# Vehicule.net
KiCad netlist of a schematic drawn in Altium Designer
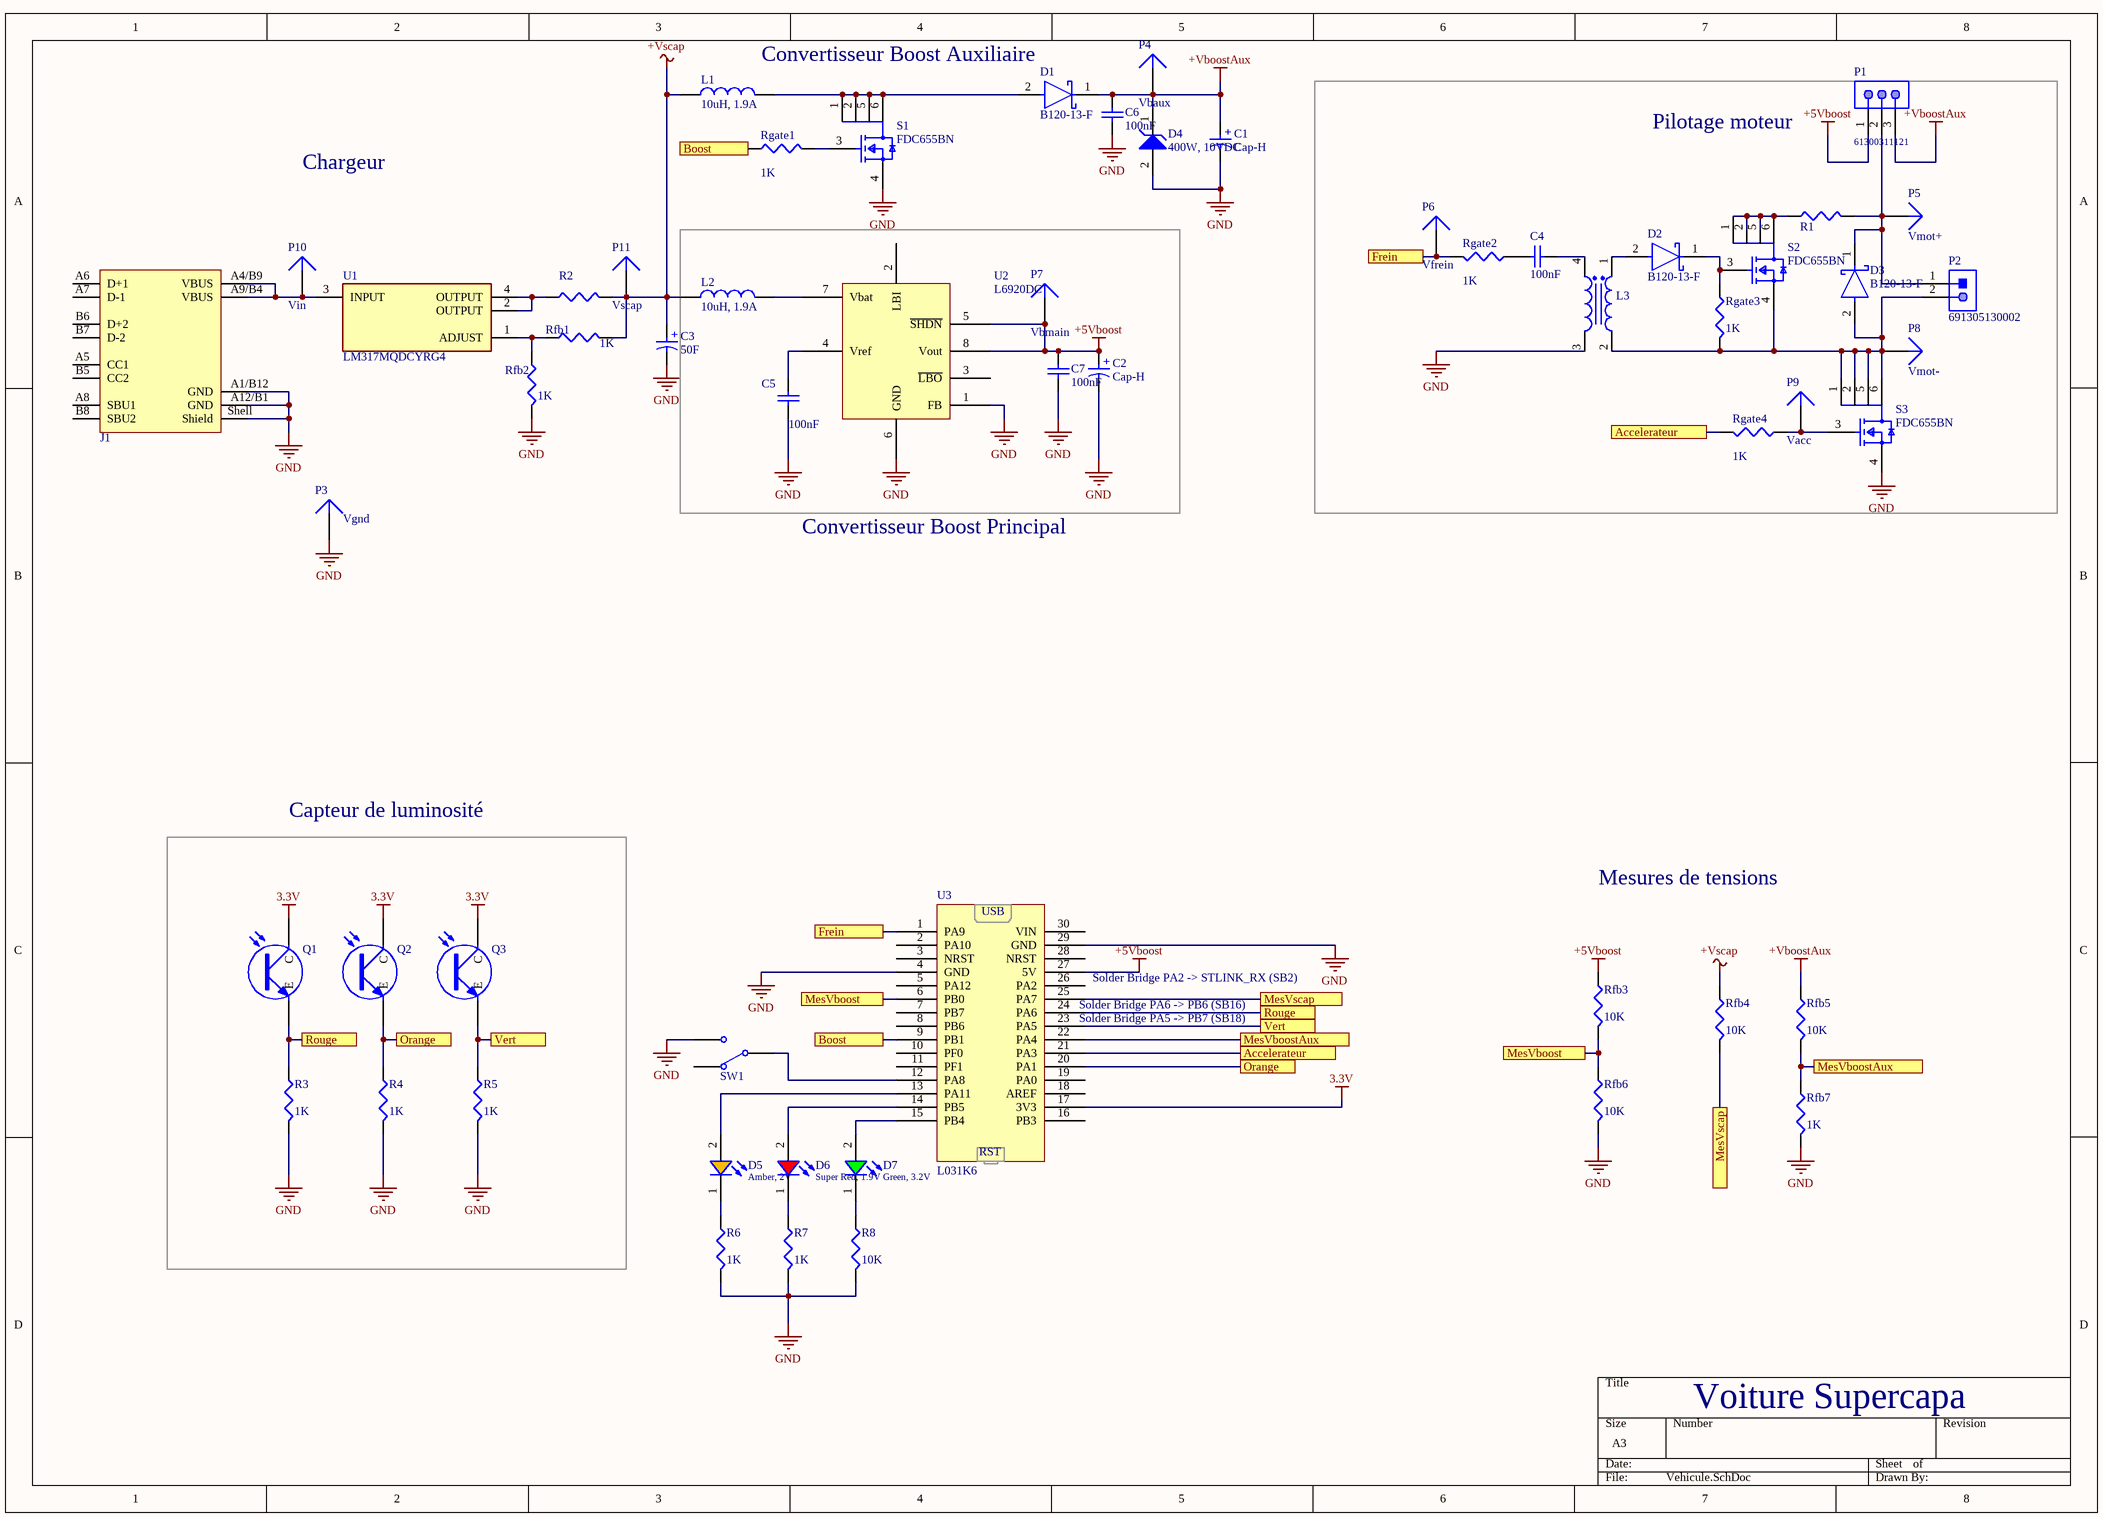
[diagram p0: Vehicule.SchDoc]

(export (version "E")
  (design (tool "Eeschema 10.0.6"))
  (components
    (comp (ref "C1")
      (value "Cap-H")
      (footprint "CAP-8x20")
      (description "Capacitor 8x20 H")
      (fields
        (field (name "MANUFACTURER PART NUMBER") "850617022002")
        (field (name "MANUFACTURER") "Wurth Elektronik")
      )
      (libsource (lib "Voiture-Supercap") (part "CAP-WE-8X20H"))
    )
    (comp (ref "C2")
      (value "Cap-H")
      (footprint "CAP-8x20")
      (description "Capacitor 8x20 H")
      (fields
        (field (name "MANUFACTURER PART NUMBER") "850617022002")
        (field (name "MANUFACTURER") "Wurth Elektronik")
      )
      (libsource (lib "Voiture-Supercap") (part "CAP-WE-8X20H"))
    )
    (comp (ref "C3")
      (value "50F")
      (footprint "SuperCap Couchee")
      (description "WCAP-STSC Supercapacitors (EDLCs), THT, D18 x H40mm, 50F, 2.7VDC")
      (fields
        (field (name "MANUFACTURER PART NUMBER") "850617022002")
        (field (name "MANUFACTURER") "Wurth Elektronik")
      )
      (libsource (lib "Voiture-Supercap") (part "850617022002"))
    )
    (comp (ref "C4")
      (value "100nF")
      (footprint "WCAP-CSGP_0805_L2W1.25H0.8_Reflow")
      (description "WCAP-CSGP Multilayer Ceramic Chip Capacitor, General Purpose, size 0805, X7R, 100nF, 25VDC")
      (fields
        (field (name "MANUFACTURER PART NUMBER") "885012207072")
        (field (name "MANUFACTURER") "Wurth Elektronik")
      )
      (libsource (lib "Altium_WCAP-CSGP (rev22f)") (part "885012207072"))
    )
    (comp (ref "C5")
      (value "100nF")
      (footprint "WCAP-CSGP_0805_L2W1.25H0.8_Reflow")
      (description "WCAP-CSGP Multilayer Ceramic Chip Capacitor, General Purpose, size 0805, X7R, 100nF, 25VDC")
      (fields
        (field (name "MANUFACTURER PART NUMBER") "885012207072")
        (field (name "MANUFACTURER") "Wurth Elektronik")
      )
      (libsource (lib "Altium_WCAP-CSGP (rev22f)") (part "885012207072"))
    )
    (comp (ref "C6")
      (value "100nF")
      (footprint "WCAP-CSGP_0805_L2W1.25H0.8_Reflow")
      (description "WCAP-CSGP Multilayer Ceramic Chip Capacitor, General Purpose, size 0805, X7R, 100nF, 25VDC")
      (fields
        (field (name "MANUFACTURER PART NUMBER") "885012207072")
        (field (name "MANUFACTURER") "Wurth Elektronik")
      )
      (libsource (lib "Altium_WCAP-CSGP (rev22f)") (part "885012207072"))
    )
    (comp (ref "C7")
      (value "100nF")
      (footprint "WCAP-CSGP_0805_L2W1.25H0.8_Reflow")
      (description "WCAP-CSGP Multilayer Ceramic Chip Capacitor, General Purpose, size 0805, X7R, 100nF, 25VDC")
      (fields
        (field (name "MANUFACTURER PART NUMBER") "885012207072")
        (field (name "MANUFACTURER") "Wurth Elektronik")
      )
      (libsource (lib "Altium_WCAP-CSGP (rev22f)") (part "885012207072"))
    )
    (comp (ref "D1")
      (value "B120-13-F")
      (footprint "FP-SMA-MFG")
      (description "DIODE SCHOTTKY 20V 1A SMA")
      (fields
        (field (name "MANUFACTURER") "Diodes Inc.")
        (field (name "OCTOPART") "https://octopart.com/b120-13-f-diodes+inc.-40148653")
      )
      (libsource (lib "Altium Content Vault") (part "1d6ec82d83fb6aee721767c19dac4b9"))
    )
    (comp (ref "D2")
      (value "B120-13-F")
      (footprint "FP-SMA-MFG")
      (description "DIODE SCHOTTKY 20V 1A SMA")
      (fields
        (field (name "MANUFACTURER") "Diodes Inc.")
        (field (name "OCTOPART") "https://octopart.com/b120-13-f-diodes+inc.-40148653")
      )
      (libsource (lib "Altium Content Vault") (part "1d6ec82d83fb6aee721767c19dac4b9"))
    )
    (comp (ref "D3")
      (value "B120-13-F")
      (footprint "FP-SMA-MFG")
      (description "DIODE SCHOTTKY 20V 1A SMA")
      (fields
        (field (name "MANUFACTURER") "Diodes Inc.")
        (field (name "OCTOPART") "https://octopart.com/b120-13-f-diodes+inc.-40148653")
      )
      (libsource (lib "Altium Content Vault") (part "1d6ec82d83fb6aee721767c19dac4b9"))
    )
    (comp (ref "D4")
      (value "400W, 10VDC")
      (footprint "WE-TVSP_DO-214AC_Unidirectional")
      (description "WE-TVSP SMT Power TVS Diode, DO-214AC, 400W, 10VDC, Unidirectional")
      (fields
        (field (name "MANUFACTURER") "Wurth Elektronik")
        (field (name "MANUFACTURER PART NUMBER") "824500101")
      )
      (libsource (lib "Altium_WE-TVSP (rev20b)") (part "824500101"))
    )
    (comp (ref "D5")
      (value "Amber, 2V")
      (footprint "WL-SMCW_0805")
      (description "WL-SMCW SMT Mono-color Chip LED Waterclear, size 0805, Amber, 2V, 140deg")
      (fields
        (field (name "PART NUMBER") "150080AS75000")
        (field (name "MANUFACTURER") "Wurth Elektronik")
        (field (name "PUBLISHER") "Wurth Elektronik")
      )
      (libsource (lib "WL-SMCW SMT Mono-color Chip LED Waterclear") (part "150080AS75000"))
    )
    (comp (ref "D6")
      (value "Super Red, 1.9V")
      (footprint "WL-SMCW_0805")
      (description "WL-SMCW SMT Mono-color Chip LED Waterclear, size 0805, Super Red, 1.9V, 140deg")
      (fields
        (field (name "PART NUMBER") "150080SS75000")
        (field (name "MANUFACTURER") "Wurth Elektronik")
        (field (name "PUBLISHER") "Wurth Elektronik")
      )
      (libsource (lib "WL-SMCW SMT Mono-color Chip LED Waterclear") (part "150080SS75000"))
    )
    (comp (ref "D7")
      (value "Green, 3.2V")
      (footprint "WL-SMCW_0805")
      (description "WL-SMCW SMT Mono-color Chip LED Waterclear, size 0805, Green, 3.2V, 140deg")
      (fields
        (field (name "PART NUMBER") "150080GS75000")
        (field (name "MANUFACTURER") "Wurth Elektronik")
        (field (name "PUBLISHER") "Wurth Elektronik")
      )
      (libsource (lib "WL-SMCW SMT Mono-color Chip LED Waterclear") (part "150080GS75000"))
    )
    (comp (ref "J1")
      (value "629722000214")
      (footprint "629722000214")
      (description "WR-USB 2.0 Type C, Receptacle, Horizontal, SMT")
      (fields (field (name "MANUFACTURER") "Wurth Elektronik"))
      (libsource (lib "Altium_WR-USB (rev22b)") (part "629722000214"))
    )
    (comp (ref "L1")
      (value "10uH, 1.9A")
      (footprint "WE-PD_6033R")
      (description "WE-PD SMT Power Inductor, size 6033R, 10uH, 1.9A")
      (fields
        (field (name "MANUFACTURER") "Wurth Elektronik")
        (field (name "MANUFACTURER PART NUMBER") "744778510")
      )
      (libsource (lib "WE-PD SMT Power Inductor") (part "744778510"))
    )
    (comp (ref "L2")
      (value "10uH, 1.9A")
      (footprint "WE-PD_6033R")
      (description "WE-PD SMT Power Inductor, size 6033R, 10uH, 1.9A")
      (fields
        (field (name "MANUFACTURER") "Wurth Elektronik")
        (field (name "MANUFACTURER PART NUMBER") "744778510")
      )
      (libsource (lib "WE-PD SMT Power Inductor") (part "744778510"))
    )
    (comp (ref "L3")
      (value "10µH / 90µH")
      (footprint "WE-MTCI_5030")
      (description "WE-MTCI SMT Multi-Turn Ratio coupled Inductor, size 5030, 1:3, 10µH / 90µH, 0.95A")
      (fields
        (field (name "MANUFACTURER PART NUMBER") "744889030100")
        (field (name "MANUFACTURER") "Wurth Elektronik")
      )
      (libsource (lib "Altium_WE-MTCI (rev22b)") (part "744889030100"))
    )
    (comp (ref "P1")
      (value "61300311121")
      (footprint "61300311121")
      (description "WR-PHD Pin Header, THT, pitch 2.54mm, Single Row, Vertical, 3p")
      (fields (field (name "MANUFACTURER") "Wurth Elektronik"))
      (libsource (lib "Altium_WR-PHD (rev20a)") (part "61300311121"))
    )
    (comp (ref "P2")
      (value "691305130002")
      (footprint "691305130002")
      (description "WR-TBL Serie 3051 Vertical PCB Header, Pluggable, pitch 3.5mm, 2p")
      (fields (field (name "MANUFACTURER") "Wurth Elektronik") (field (name "PUBLISHER") "Wurth Elektronik"))
      (libsource (lib "WR-TBL (rev19a)") (part "691305130002"))
    )
    (comp (ref "P3")
      (value "Vgnd")
      (footprint "PIN1")
      (description "Plug")
      (fields
        (field (name "MANUFACTURER") "GENERIC")
        (field (name "MANUFACTURER PART NUMBER") "NC")
        (field (name "PUBLISHER") "Altium Limited")
      )
      (libsource (lib "Miscellaneous Connectors") (part "Plug"))
    )
    (comp (ref "P4")
      (value "Vbaux")
      (footprint "PIN1")
      (description "Plug")
      (fields
        (field (name "MANUFACTURER") "GENERIC")
        (field (name "MANUFACTURER PART NUMBER") "NC")
        (field (name "PUBLISHER") "Altium Limited")
      )
      (libsource (lib "Miscellaneous Connectors") (part "Plug"))
    )
    (comp (ref "P5")
      (value "Vmot+")
      (footprint "PIN1")
      (description "Plug")
      (fields
        (field (name "MANUFACTURER") "GENERIC")
        (field (name "MANUFACTURER PART NUMBER") "NC")
        (field (name "PUBLISHER") "Altium Limited")
      )
      (libsource (lib "Miscellaneous Connectors") (part "Plug"))
    )
    (comp (ref "P6")
      (value "Vfrein")
      (footprint "PIN1")
      (description "Plug")
      (fields
        (field (name "MANUFACTURER") "GENERIC")
        (field (name "MANUFACTURER PART NUMBER") "NC")
        (field (name "PUBLISHER") "Altium Limited")
      )
      (libsource (lib "Miscellaneous Connectors") (part "Plug"))
    )
    (comp (ref "P7")
      (value "Vbmain")
      (footprint "PIN1")
      (description "Plug")
      (fields
        (field (name "MANUFACTURER") "GENERIC")
        (field (name "MANUFACTURER PART NUMBER") "NC")
        (field (name "PUBLISHER") "Altium Limited")
      )
      (libsource (lib "Miscellaneous Connectors") (part "Plug"))
    )
    (comp (ref "P8")
      (value "Vmot-")
      (footprint "PIN1")
      (description "Plug")
      (fields
        (field (name "MANUFACTURER") "GENERIC")
        (field (name "MANUFACTURER PART NUMBER") "NC")
        (field (name "PUBLISHER") "Altium Limited")
      )
      (libsource (lib "Miscellaneous Connectors") (part "Plug"))
    )
    (comp (ref "P9")
      (value "Vacc")
      (footprint "PIN1")
      (description "Plug")
      (fields
        (field (name "MANUFACTURER") "GENERIC")
        (field (name "MANUFACTURER PART NUMBER") "NC")
        (field (name "PUBLISHER") "Altium Limited")
      )
      (libsource (lib "Miscellaneous Connectors") (part "Plug"))
    )
    (comp (ref "P10")
      (value "Vin")
      (footprint "PIN1")
      (description "Plug")
      (fields
        (field (name "MANUFACTURER") "GENERIC")
        (field (name "MANUFACTURER PART NUMBER") "NC")
        (field (name "PUBLISHER") "Altium Limited")
      )
      (libsource (lib "Miscellaneous Connectors") (part "Plug"))
    )
    (comp (ref "P11")
      (value "Vscap")
      (footprint "PIN1")
      (description "Plug")
      (fields
        (field (name "MANUFACTURER") "GENERIC")
        (field (name "MANUFACTURER PART NUMBER") "NC")
        (field (name "PUBLISHER") "Altium Limited")
      )
      (libsource (lib "Miscellaneous Connectors") (part "Plug"))
    )
    (comp (ref "Q1")
      (value "1540032NA3090")
      (footprint "WL-TTRW_D3.85H5.3")
      (description "WL-TTRW THT Phototransistor Round Waterclear, D3.85H5.3mm, 400-1100nm, 5mA, 30°")
      (fields (field (name "MANUFACTURER") "Wurth Elektronik"))
      (libsource (lib "Altium_WL-TTRW (rev22b)") (part "1540032NA3090"))
    )
    (comp (ref "Q2")
      (value "1540032NA3090")
      (footprint "WL-TTRW_D3.85H5.3")
      (description "WL-TTRW THT Phototransistor Round Waterclear, D3.85H5.3mm, 400-1100nm, 5mA, 30°")
      (fields (field (name "MANUFACTURER") "Wurth Elektronik"))
      (libsource (lib "Altium_WL-TTRW (rev22b)") (part "1540032NA3090"))
    )
    (comp (ref "Q3")
      (value "1540032NA3090")
      (footprint "WL-TTRW_D3.85H5.3")
      (description "WL-TTRW THT Phototransistor Round Waterclear, D3.85H5.3mm, 400-1100nm, 5mA, 30°")
      (fields (field (name "MANUFACTURER") "Wurth Elektronik"))
      (libsource (lib "Altium_WL-TTRW (rev22b)") (part "1540032NA3090"))
    )
    (comp (ref "R1")
      (value "3.3Ω")
      (footprint "WRIS-KSKE_2512_L6.3W3.2H0.6")
      (description "WRIS-KSKE Thick Film Resistor, SMT, size 2512, 1W, 3.3Ω, +/-1%")
      (fields
        (field (name "MANUFACTURER PART NUMBER") "560050363012")
        (field (name "MANUFACTURER") "Wurth Elektronik")
      )
      (libsource (lib "Altium_WRIS-KSKE (rev22a)") (part "560050363012"))
    )
    (comp (ref "R2")
      (value "3.3Ω")
      (footprint "WRIS-KSKE_2512_L6.3W3.2H0.6")
      (description "WRIS-KSKE Thick Film Resistor, SMT, size 2512, 1W, 3.3Ω, +/-1%")
      (fields
        (field (name "MANUFACTURER PART NUMBER") "560050363012")
        (field (name "MANUFACTURER") "Wurth Elektronik")
      )
      (libsource (lib "Altium_WRIS-KSKE (rev22a)") (part "560050363012"))
    )
    (comp (ref "R3")
      (value "1K")
      (footprint "R0805")
      (description "Resistor")
      (fields
        (field (name "MANUFACTURER") "GENERIC")
        (field (name "MANUFACTURER PART NUMBER") "RESISTANCE-0805-1K")
        (field (name "PUBLISHER") "Altium Limited")
      )
      (libsource (lib "Voiture-Supercap") (part "R0805"))
    )
    (comp (ref "R4")
      (value "1K")
      (footprint "R0805")
      (description "Resistor")
      (fields
        (field (name "MANUFACTURER") "GENERIC")
        (field (name "MANUFACTURER PART NUMBER") "RESISTANCE-0805-1K")
        (field (name "PUBLISHER") "Altium Limited")
      )
      (libsource (lib "Voiture-Supercap") (part "R0805"))
    )
    (comp (ref "R5")
      (value "1K")
      (footprint "R0805")
      (description "Resistor")
      (fields
        (field (name "MANUFACTURER") "GENERIC")
        (field (name "MANUFACTURER PART NUMBER") "RESISTANCE-0805-1K")
        (field (name "PUBLISHER") "Altium Limited")
      )
      (libsource (lib "Voiture-Supercap") (part "R0805"))
    )
    (comp (ref "R6")
      (value "1K")
      (footprint "R0805")
      (description "Resistor")
      (fields
        (field (name "MANUFACTURER") "GENERIC")
        (field (name "MANUFACTURER PART NUMBER") "RESISTANCE-0805-1K")
        (field (name "PUBLISHER") "Altium Limited")
      )
      (libsource (lib "Voiture-Supercap") (part "R0805"))
    )
    (comp (ref "R7")
      (value "1K")
      (footprint "R0805")
      (description "Resistor")
      (fields
        (field (name "MANUFACTURER") "GENERIC")
        (field (name "MANUFACTURER PART NUMBER") "RESISTANCE-0805-1K")
        (field (name "PUBLISHER") "Altium Limited")
      )
      (libsource (lib "Voiture-Supercap") (part "R0805"))
    )
    (comp (ref "R8")
      (value "10K")
      (footprint "R0805")
      (description "Resistor")
      (fields
        (field (name "MANUFACTURER") "GENERIC")
        (field (name "MANUFACTURER PART NUMBER") "RESISTANCE-0805-10K")
        (field (name "PUBLISHER") "Altium Limited")
      )
      (libsource (lib "Voiture-Supercap") (part "R0805"))
    )
    (comp (ref "Rfb1")
      (value "1K")
      (footprint "R0805")
      (description "Resistor")
      (fields
        (field (name "MANUFACTURER") "GENERIC")
        (field (name "MANUFACTURER PART NUMBER") "RESISTANCE-0805-1K")
        (field (name "PUBLISHER") "Altium Limited")
      )
      (libsource (lib "Voiture-Supercap") (part "R0805"))
    )
    (comp (ref "Rfb2")
      (value "1K")
      (footprint "R0805")
      (description "Resistor")
      (fields
        (field (name "MANUFACTURER") "GENERIC")
        (field (name "MANUFACTURER PART NUMBER") "RESISTANCE-0805-1K")
        (field (name "PUBLISHER") "Altium Limited")
      )
      (libsource (lib "Voiture-Supercap") (part "R0805"))
    )
    (comp (ref "Rfb3")
      (value "10K")
      (footprint "R0805")
      (description "Resistor")
      (fields
        (field (name "MANUFACTURER") "GENERIC")
        (field (name "MANUFACTURER PART NUMBER") "RESISTANCE-0805-10K")
        (field (name "PUBLISHER") "Altium Limited")
      )
      (libsource (lib "Voiture-Supercap") (part "R0805"))
    )
    (comp (ref "Rfb4")
      (value "10K")
      (footprint "R0805")
      (description "Resistor")
      (fields
        (field (name "MANUFACTURER") "GENERIC")
        (field (name "MANUFACTURER PART NUMBER") "RESISTANCE-0805-10K")
        (field (name "PUBLISHER") "Altium Limited")
      )
      (libsource (lib "Voiture-Supercap") (part "R0805"))
    )
    (comp (ref "Rfb5")
      (value "10K")
      (footprint "R0805")
      (description "Resistor")
      (fields
        (field (name "MANUFACTURER") "GENERIC")
        (field (name "MANUFACTURER PART NUMBER") "RESISTANCE-0805-10K")
        (field (name "PUBLISHER") "Altium Limited")
      )
      (libsource (lib "Voiture-Supercap") (part "R0805"))
    )
    (comp (ref "Rfb6")
      (value "10K")
      (footprint "R0805")
      (description "Resistor")
      (fields
        (field (name "MANUFACTURER") "GENERIC")
        (field (name "MANUFACTURER PART NUMBER") "RESISTANCE-0805-10K")
        (field (name "PUBLISHER") "Altium Limited")
      )
      (libsource (lib "Voiture-Supercap") (part "R0805"))
    )
    (comp (ref "Rfb7")
      (value "1K")
      (footprint "R0805")
      (description "Resistor")
      (fields
        (field (name "MANUFACTURER") "GENERIC")
        (field (name "MANUFACTURER PART NUMBER") "RESISTANCE-0805-1K")
        (field (name "PUBLISHER") "Altium Limited")
      )
      (libsource (lib "Voiture-Supercap") (part "R0805"))
    )
    (comp (ref "Rgate1")
      (value "1K")
      (footprint "R0805")
      (description "Resistor")
      (fields
        (field (name "MANUFACTURER") "GENERIC")
        (field (name "MANUFACTURER PART NUMBER") "RESISTANCE-0805-1K")
        (field (name "PUBLISHER") "Altium Limited")
      )
      (libsource (lib "Voiture-Supercap") (part "R0805"))
    )
    (comp (ref "Rgate2")
      (value "1K")
      (footprint "R0805")
      (description "Resistor")
      (fields
        (field (name "MANUFACTURER") "GENERIC")
        (field (name "MANUFACTURER PART NUMBER") "RESISTANCE-0805-1K")
        (field (name "PUBLISHER") "Altium Limited")
      )
      (libsource (lib "Voiture-Supercap") (part "R0805"))
    )
    (comp (ref "Rgate3")
      (value "1K")
      (footprint "R0805")
      (description "Resistor")
      (fields
        (field (name "MANUFACTURER") "GENERIC")
        (field (name "MANUFACTURER PART NUMBER") "RESISTANCE-0805-1K")
        (field (name "PUBLISHER") "Altium Limited")
      )
      (libsource (lib "Voiture-Supercap") (part "R0805"))
    )
    (comp (ref "Rgate4")
      (value "1K")
      (footprint "R0805")
      (description "Resistor")
      (fields
        (field (name "MANUFACTURER") "GENERIC")
        (field (name "MANUFACTURER PART NUMBER") "RESISTANCE-0805-1K")
        (field (name "PUBLISHER") "Altium Limited")
      )
      (libsource (lib "Voiture-Supercap") (part "R0805"))
    )
    (comp (ref "S1")
      (value "FDC655BN")
      (footprint "FP-419BL-MFG")
      (description "MOSFET N-CH 30V 6.3A SSOT-6")
      (fields
        (field (name "OCTOPART") "https://octopart.com/fdc655bn-on+semiconductor-84325765")
        (field (name "MANUFACTURER") "ON Semiconductor")
      )
      (libsource (lib "Altium Content Vault") (part "713c02021b26d64843484fe217aab72"))
    )
    (comp (ref "S2")
      (value "FDC655BN")
      (footprint "FP-419BL-MFG")
      (description "MOSFET N-CH 30V 6.3A SSOT-6")
      (fields
        (field (name "OCTOPART") "https://octopart.com/fdc655bn-on+semiconductor-84325765")
        (field (name "MANUFACTURER") "ON Semiconductor")
      )
      (libsource (lib "Altium Content Vault") (part "713c02021b26d64843484fe217aab72"))
    )
    (comp (ref "S3")
      (value "FDC655BN")
      (footprint "FP-419BL-MFG")
      (description "MOSFET N-CH 30V 6.3A SSOT-6")
      (fields
        (field (name "OCTOPART") "https://octopart.com/fdc655bn-on+semiconductor-84325765")
        (field (name "MANUFACTURER") "ON Semiconductor")
      )
      (libsource (lib "Altium Content Vault") (part "713c02021b26d64843484fe217aab72"))
    )
    (comp (ref "SW1")
      (value "450404015514")
      (footprint "450404015514")
      (description "WS-SLSU Mini Slide Switch, Same Side Connection Side Push, SPDT, 5VDC, 300mA, 240g")
      (fields (field (name "MANUFACTURER") "Wurth Elektronik"))
      (libsource (lib "Altium_WS-SLSU (rev22a)") (part "450404015514"))
    )
    (comp (ref "U1")
      (value "LM317MQDCYRG4")
      (footprint "FP-DCY0004A-IPC_B")
      (description "IC REG LIN POS ADJ 500MA SOT223")
      (fields (field (name "MANUFACTURER") "TEXAS INSTRUMENTS"))
      (libsource (lib "Altium Content Vault") (part "64889274e516db7cba8a73b447600b9"))
    )
    (comp (ref "U2")
      (value "L6920DC")
      (footprint "TSOP65P500X110-8N")
      (fields (field (name "MANUFACTURER") "STMICROELECTRONICS"))
      (libsource (lib "Voiture-Supercap") (part "L6920DC"))
    )
    (comp (ref "U3")
      (value "L031K6")
      (footprint "STM-Nano")
      (fields
        (field (name "MANUFACTURER") "STMICROELECTRONICS")
        (field (name "MANUFACTURER PART NUMBER") "NUCLEO-L031K6")
      )
      (libsource (lib "Voiture-Supercap") (part "STM32-NUCLEO-L031K6"))
    )
  )
  (nets
    (net (code "1") (name "+5Vboost") (class "Default")
      (node (ref "C2") (pin "1") (pinfunction "P_1") (pintype "passive"))
      (node (ref "C7") (pin "1") (pinfunction "1_1") (pintype "passive"))
      (node (ref "P1") (pin "1") (pinfunction "1_1") (pintype "passive"))
      (node (ref "P7") (pin "1") (pinfunction "1_1") (pintype "passive"))
      (node (ref "Rfb3") (pin "1") (pinfunction "1_1") (pintype "passive"))
      (node (ref "U2") (pin "5") (pinfunction "~{SHDN}_5") (pintype "passive"))
      (node (ref "U2") (pin "8") (pinfunction "Vout_8") (pintype "passive"))
      (node (ref "U3") (pin "27") (pinfunction "5V_27") (pintype "passive"))
    )
    (net (code "2") (name "+VboostAux") (class "Default")
      (node (ref "C1") (pin "1") (pinfunction "P_1") (pintype "passive"))
      (node (ref "C6") (pin "1") (pinfunction "1_1") (pintype "passive"))
      (node (ref "D1") (pin "1") (pinfunction "C_1") (pintype "passive"))
      (node (ref "D4") (pin "1") (pinfunction "K_1") (pintype "passive"))
      (node (ref "P1") (pin "3") (pinfunction "3_3") (pintype "passive"))
      (node (ref "P4") (pin "1") (pinfunction "1_1") (pintype "passive"))
      (node (ref "Rfb5") (pin "1") (pinfunction "1_1") (pintype "passive"))
    )
    (net (code "3") (name "+Vscap") (class "Default")
      (node (ref "C3") (pin "1") (pinfunction "P_1") (pintype "passive"))
      (node (ref "L1") (pin "1") (pinfunction "1_1") (pintype "passive"))
      (node (ref "L2") (pin "1") (pinfunction "1_1") (pintype "passive"))
      (node (ref "P11") (pin "1") (pinfunction "1_1") (pintype "passive"))
      (node (ref "R2") (pin "2") (pinfunction "2_2") (pintype "passive"))
      (node (ref "Rfb1") (pin "2") (pinfunction "2_2") (pintype "passive"))
      (node (ref "Rfb4") (pin "1") (pinfunction "1_1") (pintype "passive"))
    )
    (net (code "4") (name "/Accelerateur") (class "Default")
      (node (ref "Rgate4") (pin "2") (pinfunction "2_2") (pintype "passive"))
      (node (ref "U3") (pin "21") (pinfunction "PA3_21") (pintype "passive"))
    )
    (net (code "5") (name "/Boost") (class "Default")
      (node (ref "Rgate1") (pin "1") (pinfunction "1_1") (pintype "passive"))
      (node (ref "U3") (pin "9") (pinfunction "PB1_9") (pintype "passive"))
    )
    (net (code "6") (name "/Frein") (class "Default")
      (node (ref "P6") (pin "1") (pinfunction "1_1") (pintype "passive"))
      (node (ref "Rgate2") (pin "2") (pinfunction "2_2") (pintype "passive"))
      (node (ref "U3") (pin "1") (pinfunction "PA9_1") (pintype "passive"))
    )
    (net (code "7") (name "/MesVboost") (class "Default")
      (node (ref "Rfb3") (pin "2") (pinfunction "2_2") (pintype "passive"))
      (node (ref "Rfb6") (pin "1") (pinfunction "1_1") (pintype "passive"))
      (node (ref "U3") (pin "6") (pinfunction "PB0_6") (pintype "passive"))
    )
    (net (code "8") (name "/MesVboostAux") (class "Default")
      (node (ref "Rfb5") (pin "2") (pinfunction "2_2") (pintype "passive"))
      (node (ref "Rfb7") (pin "1") (pinfunction "1_1") (pintype "passive"))
      (node (ref "U3") (pin "22") (pinfunction "PA4_22") (pintype "passive"))
    )
    (net (code "9") (name "/MesVscap") (class "Default")
      (node (ref "Rfb4") (pin "2") (pinfunction "2_2") (pintype "passive"))
      (node (ref "U3") (pin "25") (pinfunction "PA7_25") (pintype "passive"))
    )
    (net (code "10") (name "/Orange") (class "Default")
      (node (ref "Q2") (pin "2") (pinfunction "E_2") (pintype "passive"))
      (node (ref "R4") (pin "1") (pinfunction "1_1") (pintype "passive"))
      (node (ref "U3") (pin "20") (pinfunction "PA1_20") (pintype "passive"))
    )
    (net (code "11") (name "/Rouge") (class "Default")
      (node (ref "Q1") (pin "2") (pinfunction "E_2") (pintype "passive"))
      (node (ref "R3") (pin "1") (pinfunction "1_1") (pintype "passive"))
      (node (ref "U3") (pin "24") (pinfunction "PA6_24") (pintype "passive"))
    )
    (net (code "12") (name "/Vert") (class "Default")
      (node (ref "Q3") (pin "2") (pinfunction "E_2") (pintype "passive"))
      (node (ref "R5") (pin "1") (pinfunction "1_1") (pintype "passive"))
      (node (ref "U3") (pin "23") (pinfunction "PA5_23") (pintype "passive"))
    )
    (net (code "13") (name "3.3V") (class "Default")
      (node (ref "Q1") (pin "1") (pinfunction "C_1") (pintype "passive"))
      (node (ref "Q2") (pin "1") (pinfunction "C_1") (pintype "passive"))
      (node (ref "Q3") (pin "1") (pinfunction "C_1") (pintype "passive"))
      (node (ref "U3") (pin "17") (pinfunction "3V3_17") (pintype "passive"))
    )
    (net (code "14") (name "GND") (class "Default")
      (node (ref "C1") (pin "2") (pinfunction "N_2") (pintype "passive"))
      (node (ref "C2") (pin "2") (pinfunction "N_2") (pintype "passive"))
      (node (ref "C3") (pin "2") (pinfunction "N_2") (pintype "passive"))
      (node (ref "C5") (pin "1") (pinfunction "1_1") (pintype "passive"))
      (node (ref "C6") (pin "2") (pinfunction "2_2") (pintype "passive"))
      (node (ref "C7") (pin "2") (pinfunction "2_2") (pintype "passive"))
      (node (ref "D4") (pin "2") (pinfunction "A_2") (pintype "passive"))
      (node (ref "J1") (pin "A1/B12") (pinfunction "GND_A1/B12") (pintype "passive"))
      (node (ref "J1") (pin "A12/B1") (pinfunction "GND_A12/B1") (pintype "passive"))
      (node (ref "J1") (pin "Shell") (pinfunction "Shield_Shell") (pintype "passive"))
      (node (ref "L3") (pin "3") (pinfunction "3_3") (pintype "passive"))
      (node (ref "P3") (pin "1") (pinfunction "1_1") (pintype "passive"))
      (node (ref "R3") (pin "2") (pinfunction "2_2") (pintype "passive"))
      (node (ref "R4") (pin "2") (pinfunction "2_2") (pintype "passive"))
      (node (ref "R5") (pin "2") (pinfunction "2_2") (pintype "passive"))
      (node (ref "R6") (pin "2") (pinfunction "2_2") (pintype "passive"))
      (node (ref "R7") (pin "2") (pinfunction "2_2") (pintype "passive"))
      (node (ref "R8") (pin "2") (pinfunction "2_2") (pintype "passive"))
      (node (ref "Rfb2") (pin "2") (pinfunction "2_2") (pintype "passive"))
      (node (ref "Rfb6") (pin "2") (pinfunction "2_2") (pintype "passive"))
      (node (ref "Rfb7") (pin "2") (pinfunction "2_2") (pintype "passive"))
      (node (ref "S1") (pin "4") (pinfunction "S_4") (pintype "passive"))
      (node (ref "S3") (pin "4") (pinfunction "S_4") (pintype "passive"))
      (node (ref "SW1") (pin "L2") (pinfunction "L2_L2") (pintype "passive"))
      (node (ref "U2") (pin "1") (pinfunction "FB_1") (pintype "passive"))
      (node (ref "U2") (pin "6") (pinfunction "GND_6") (pintype "passive"))
      (node (ref "U3") (pin "29") (pinfunction "GND_29") (pintype "passive"))
      (node (ref "U3") (pin "4") (pinfunction "GND_4") (pintype "passive"))
    )
    (net (code "15") (name "Net-(C4-Pad1)") (class "Default")
      (node (ref "C4") (pin "1") (pinfunction "1_1") (pintype "passive"))
      (node (ref "L3") (pin "4") (pinfunction "4_4") (pintype "passive"))
    )
    (net (code "16") (name "Net-(C4-Pad2)") (class "Default")
      (node (ref "C4") (pin "2") (pinfunction "2_2") (pintype "passive"))
      (node (ref "Rgate2") (pin "1") (pinfunction "1_1") (pintype "passive"))
    )
    (net (code "17") (name "Net-(D1-A)") (class "Default")
      (node (ref "D1") (pin "2") (pinfunction "A_2") (pintype "passive"))
      (node (ref "L1") (pin "2") (pinfunction "2_2") (pintype "passive"))
      (node (ref "S1") (pin "1") (pinfunction "D_1") (pintype "passive"))
      (node (ref "S1") (pin "2") (pinfunction "D_2") (pintype "passive"))
      (node (ref "S1") (pin "5") (pinfunction "D_5") (pintype "passive"))
      (node (ref "S1") (pin "6") (pinfunction "D_6") (pintype "passive"))
    )
    (net (code "18") (name "Net-(D2-A)") (class "Default")
      (node (ref "D2") (pin "2") (pinfunction "A_2") (pintype "passive"))
      (node (ref "L3") (pin "1") (pinfunction "1_1") (pintype "passive"))
    )
    (net (code "19") (name "Net-(D2-C)") (class "Default")
      (node (ref "D2") (pin "1") (pinfunction "C_1") (pintype "passive"))
      (node (ref "Rgate3") (pin "1") (pinfunction "1_1") (pintype "passive"))
      (node (ref "S2") (pin "3") (pinfunction "G_3") (pintype "passive"))
    )
    (net (code "20") (name "Net-(D3-A)") (class "Default")
      (node (ref "D3") (pin "2") (pinfunction "A_2") (pintype "passive"))
      (node (ref "L3") (pin "2") (pinfunction "2_2") (pintype "passive"))
      (node (ref "P2") (pin "2") (pinfunction "2_2") (pintype "passive"))
      (node (ref "P8") (pin "1") (pinfunction "1_1") (pintype "passive"))
      (node (ref "Rgate3") (pin "2") (pinfunction "2_2") (pintype "passive"))
      (node (ref "S2") (pin "4") (pinfunction "S_4") (pintype "passive"))
      (node (ref "S3") (pin "1") (pinfunction "D_1") (pintype "passive"))
      (node (ref "S3") (pin "2") (pinfunction "D_2") (pintype "passive"))
      (node (ref "S3") (pin "5") (pinfunction "D_5") (pintype "passive"))
      (node (ref "S3") (pin "6") (pinfunction "D_6") (pintype "passive"))
    )
    (net (code "21") (name "Net-(D3-C)") (class "Default")
      (node (ref "D3") (pin "1") (pinfunction "C_1") (pintype "passive"))
      (node (ref "P1") (pin "2") (pinfunction "2_2") (pintype "passive"))
      (node (ref "P2") (pin "1") (pinfunction "1_1") (pintype "passive"))
      (node (ref "P5") (pin "1") (pinfunction "1_1") (pintype "passive"))
      (node (ref "R1") (pin "2") (pinfunction "2_2") (pintype "passive"))
    )
    (net (code "22") (name "Net-(D5-A)") (class "Default")
      (node (ref "D5") (pin "2") (pinfunction "A_2") (pintype "passive"))
      (node (ref "U3") (pin "13") (pinfunction "PA11_13") (pintype "passive"))
    )
    (net (code "23") (name "Net-(D5-K)") (class "Default")
      (node (ref "D5") (pin "1") (pinfunction "K_1") (pintype "passive"))
      (node (ref "R6") (pin "1") (pinfunction "1_1") (pintype "passive"))
    )
    (net (code "24") (name "Net-(D6-A)") (class "Default")
      (node (ref "D6") (pin "2") (pinfunction "A_2") (pintype "passive"))
      (node (ref "U3") (pin "14") (pinfunction "PB5_14") (pintype "passive"))
    )
    (net (code "25") (name "Net-(D6-K)") (class "Default")
      (node (ref "D6") (pin "1") (pinfunction "K_1") (pintype "passive"))
      (node (ref "R7") (pin "1") (pinfunction "1_1") (pintype "passive"))
    )
    (net (code "26") (name "Net-(D7-A)") (class "Default")
      (node (ref "D7") (pin "2") (pinfunction "A_2") (pintype "passive"))
      (node (ref "U3") (pin "15") (pinfunction "PB4_15") (pintype "passive"))
    )
    (net (code "27") (name "Net-(D7-K)") (class "Default")
      (node (ref "D7") (pin "1") (pinfunction "K_1") (pintype "passive"))
      (node (ref "R8") (pin "1") (pinfunction "1_1") (pintype "passive"))
    )
    (net (code "28") (name "Net-(R1-Pad1)") (class "Default")
      (node (ref "R1") (pin "1") (pinfunction "1_1") (pintype "passive"))
      (node (ref "S2") (pin "1") (pinfunction "D_1") (pintype "passive"))
      (node (ref "S2") (pin "2") (pinfunction "D_2") (pintype "passive"))
      (node (ref "S2") (pin "5") (pinfunction "D_5") (pintype "passive"))
      (node (ref "S2") (pin "6") (pinfunction "D_6") (pintype "passive"))
    )
    (net (code "29") (name "Net-(R2-Pad1)") (class "Default")
      (node (ref "R2") (pin "1") (pinfunction "1_1") (pintype "passive"))
      (node (ref "U1") (pin "2") (pinfunction "OUTPUT_2") (pintype "power_in"))
      (node (ref "U1") (pin "4") (pinfunction "OUTPUT_4") (pintype "power_in"))
    )
    (net (code "30") (name "Net-(S1-G)") (class "Default")
      (node (ref "Rgate1") (pin "2") (pinfunction "2_2") (pintype "passive"))
      (node (ref "S1") (pin "3") (pinfunction "G_3") (pintype "passive"))
    )
    (net (code "31") (name "Net-(S3-G)") (class "Default")
      (node (ref "P9") (pin "1") (pinfunction "1_1") (pintype "passive"))
      (node (ref "Rgate4") (pin "1") (pinfunction "1_1") (pintype "passive"))
      (node (ref "S3") (pin "3") (pinfunction "G_3") (pintype "passive"))
    )
    (net (code "32") (name "Net-(U1-ADJUST)") (class "Default")
      (node (ref "Rfb1") (pin "1") (pinfunction "1_1") (pintype "passive"))
      (node (ref "Rfb2") (pin "1") (pinfunction "1_1") (pintype "passive"))
      (node (ref "U1") (pin "1") (pinfunction "ADJUST_1") (pintype "passive"))
    )
    (net (code "33") (name "Net-(U1-INPUT)") (class "Default")
      (node (ref "J1") (pin "A4/B9") (pinfunction "VBUS_A4/B9") (pintype "passive"))
      (node (ref "J1") (pin "A9/B4") (pinfunction "VBUS_A9/B4") (pintype "passive"))
      (node (ref "P10") (pin "1") (pinfunction "1_1") (pintype "passive"))
      (node (ref "U1") (pin "3") (pinfunction "INPUT_3") (pintype "power_in"))
    )
    (net (code "34") (name "Net-(U2-Vbat)") (class "Default")
      (node (ref "L2") (pin "2") (pinfunction "2_2") (pintype "passive"))
      (node (ref "U2") (pin "7") (pinfunction "Vbat_7") (pintype "passive"))
    )
    (net (code "35") (name "Net-(U2-Vref)") (class "Default")
      (node (ref "C5") (pin "2") (pinfunction "2_2") (pintype "passive"))
      (node (ref "U2") (pin "4") (pinfunction "Vref_4") (pintype "passive"))
    )
    (net (code "36") (name "Net-(U3-PA8)") (class "Default")
      (node (ref "SW1") (pin "COM") (pinfunction "COM_COM") (pintype "passive"))
      (node (ref "U3") (pin "12") (pinfunction "PA8_12") (pintype "passive"))
    )
    (net (code "37") (name "unconnected-(J1-CC1-PadA5)") (class "Default")
      (node (ref "J1") (pin "A5") (pinfunction "CC1_A5") (pintype "passive"))
    )
    (net (code "38") (name "unconnected-(J1-CC2-PadB5)") (class "Default")
      (node (ref "J1") (pin "B5") (pinfunction "CC2_B5") (pintype "passive"))
    )
    (net (code "39") (name "unconnected-(J1-D+1-PadA6)") (class "Default")
      (node (ref "J1") (pin "A6") (pinfunction "D+1_A6") (pintype "passive"))
    )
    (net (code "40") (name "unconnected-(J1-D+2-PadB6)") (class "Default")
      (node (ref "J1") (pin "B6") (pinfunction "D+2_B6") (pintype "passive"))
    )
    (net (code "41") (name "unconnected-(J1-D-1-PadA7)") (class "Default")
      (node (ref "J1") (pin "A7") (pinfunction "D-1_A7") (pintype "passive"))
    )
    (net (code "42") (name "unconnected-(J1-D-2-PadB7)") (class "Default")
      (node (ref "J1") (pin "B7") (pinfunction "D-2_B7") (pintype "passive"))
    )
    (net (code "43") (name "unconnected-(J1-SBU1-PadA8)") (class "Default")
      (node (ref "J1") (pin "A8") (pinfunction "SBU1_A8") (pintype "passive"))
    )
    (net (code "44") (name "unconnected-(J1-SBU2-PadB8)") (class "Default")
      (node (ref "J1") (pin "B8") (pinfunction "SBU2_B8") (pintype "passive"))
    )
    (net (code "45") (name "unconnected-(SW1-PadL1)") (class "Default")
      (node (ref "SW1") (pin "L1") (pinfunction "L1_L1") (pintype "passive"))
    )
    (net (code "46") (name "unconnected-(U2-LBI-Pad2)") (class "Default")
      (node (ref "U2") (pin "2") (pinfunction "LBI_2") (pintype "passive"))
    )
    (net (code "47") (name "unconnected-(U2-~{LBO}-Pad3)") (class "Default")
      (node (ref "U2") (pin "3") (pinfunction "~{LBO}_3") (pintype "passive"))
    )
    (net (code "48") (name "unconnected-(U3-AREF-Pad18)") (class "Default")
      (node (ref "U3") (pin "18") (pinfunction "AREF_18") (pintype "passive"))
    )
    (net (code "49") (name "unconnected-(U3-NRST-Pad3)") (class "Default")
      (node (ref "U3") (pin "3") (pinfunction "NRST_3") (pintype "passive"))
    )
    (net (code "50") (name "unconnected-(U3-NRST-Pad28)") (class "Default")
      (node (ref "U3") (pin "28") (pinfunction "NRST_28") (pintype "passive"))
    )
    (net (code "51") (name "unconnected-(U3-PA0-Pad19)") (class "Default")
      (node (ref "U3") (pin "19") (pinfunction "PA0_19") (pintype "passive"))
    )
    (net (code "52") (name "unconnected-(U3-PA2-Pad26)") (class "Default")
      (node (ref "U3") (pin "26") (pinfunction "PA2_26") (pintype "passive"))
    )
    (net (code "53") (name "unconnected-(U3-PA10-Pad2)") (class "Default")
      (node (ref "U3") (pin "2") (pinfunction "PA10_2") (pintype "passive"))
    )
    (net (code "54") (name "unconnected-(U3-PA12-Pad5)") (class "Default")
      (node (ref "U3") (pin "5") (pinfunction "PA12_5") (pintype "passive"))
    )
    (net (code "55") (name "unconnected-(U3-PB3-Pad16)") (class "Default")
      (node (ref "U3") (pin "16") (pinfunction "PB3_16") (pintype "passive"))
    )
    (net (code "56") (name "unconnected-(U3-PB6-Pad8)") (class "Default")
      (node (ref "U3") (pin "8") (pinfunction "PB6_8") (pintype "passive"))
    )
    (net (code "57") (name "unconnected-(U3-PB7-Pad7)") (class "Default")
      (node (ref "U3") (pin "7") (pinfunction "PB7_7") (pintype "passive"))
    )
    (net (code "58") (name "unconnected-(U3-PF0-Pad10)") (class "Default")
      (node (ref "U3") (pin "10") (pinfunction "PF0_10") (pintype "passive"))
    )
    (net (code "59") (name "unconnected-(U3-PF1-Pad11)") (class "Default")
      (node (ref "U3") (pin "11") (pinfunction "PF1_11") (pintype "passive"))
    )
    (net (code "60") (name "unconnected-(U3-VIN-Pad30)") (class "Default")
      (node (ref "U3") (pin "30") (pinfunction "VIN_30") (pintype "passive"))
    )
  )
)
